# ard.net
KiCad netlist of a schematic drawn in EAGLE
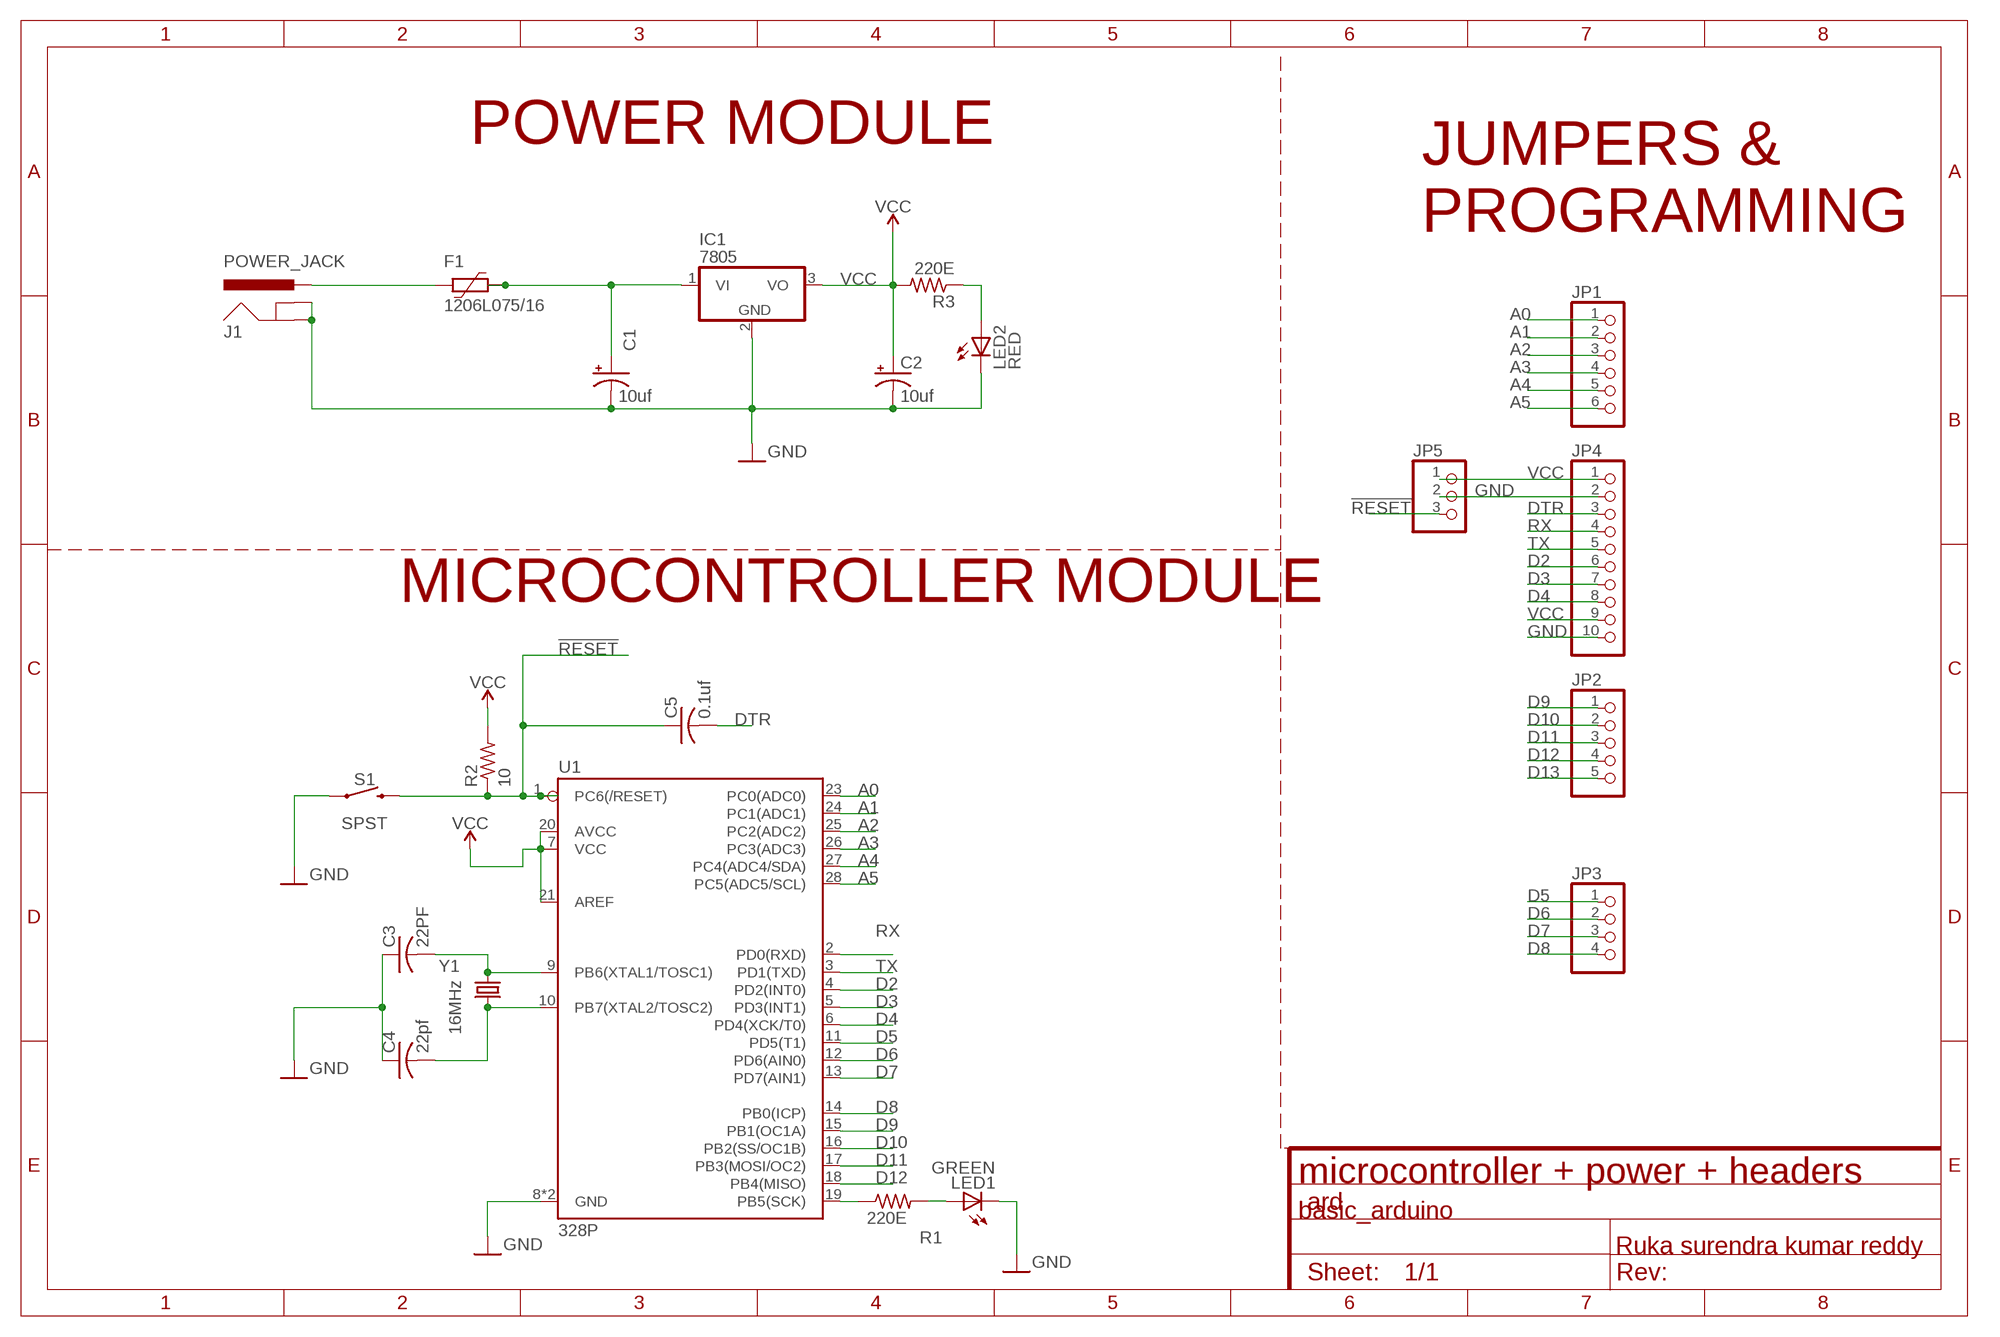
[diagram p0: schematic, sheet 1]

(export (version "E")
  (design (tool "Eeschema 10.0.6"))
  (components
    (comp (ref "C1")
      (value "10uf")
      (footprint "eagle-import:E2,5-6E")
      (libsource (lib "eagle-import") (part "CPOL-USE2,5-6E"))
    )
    (comp (ref "C2")
      (value "10uf")
      (footprint "eagle-import:E2,5-6E")
      (libsource (lib "eagle-import") (part "CPOL-USE2,5-6E"))
    )
    (comp (ref "C3")
      (value "22PF")
      (footprint "eagle-import:C025-024X044")
      (libsource (lib "eagle-import") (part "C-US025-024X044"))
    )
    (comp (ref "C4")
      (value "22pf")
      (footprint "eagle-import:C025-024X044")
      (libsource (lib "eagle-import") (part "C-US025-024X044"))
    )
    (comp (ref "C5")
      (value "0.1uf")
      (footprint "eagle-import:C025-024X044")
      (libsource (lib "eagle-import") (part "C-US025-024X044"))
    )
    (comp (ref "F1")
      (value "1206L075/16")
      (footprint "eagle-import:1206L")
      (fields (field (name "MF") "Littelfuse"))
      (libsource (lib "eagle-import") (part "?1206L075/16"))
    )
    (comp (ref "IC1")
      (value "7805")
      (footprint "eagle-import:TO220V")
      (libsource (lib "eagle-import") (part "78TV05"))
    )
    (comp (ref "J1")
      (value "POWER_JACK")
      (footprint "eagle-import:POWER_JACK_PTH")
      (libsource (lib "eagle-import") (part "POWER_JACK"))
    )
    (comp (ref "JP1")
      (value "PINHD-1X6")
      (footprint "eagle-import:1X06")
      (libsource (lib "eagle-import") (part "PINHD-1X6"))
    )
    (comp (ref "JP2")
      (value "PINHD-1X5")
      (footprint "eagle-import:1X05")
      (libsource (lib "eagle-import") (part "PINHD-1X5"))
    )
    (comp (ref "JP3")
      (value "PINHD-1X4")
      (footprint "eagle-import:1X04")
      (libsource (lib "eagle-import") (part "PINHD-1X4"))
    )
    (comp (ref "JP4")
      (value "PINHD-1X10")
      (footprint "eagle-import:1X10")
      (libsource (lib "eagle-import") (part "PINHD-1X10"))
    )
    (comp (ref "JP5")
      (value "PINHD-1X3")
      (footprint "eagle-import:1X03")
      (libsource (lib "eagle-import") (part "PINHD-1X3"))
    )
    (comp (ref "LED1")
      (value "GREEN")
      (footprint "eagle-import:LED5MM")
      (libsource (lib "eagle-import") (part "LED5MM"))
    )
    (comp (ref "LED2")
      (value "RED")
      (footprint "eagle-import:LED5MM")
      (libsource (lib "eagle-import") (part "LED5MM"))
    )
    (comp (ref "R1")
      (value "220E")
      (footprint "eagle-import:0204_7")
      (libsource (lib "eagle-import") (part "R-US_0204/7"))
    )
    (comp (ref "R2")
      (value "10")
      (footprint "eagle-import:0204_7")
      (libsource (lib "eagle-import") (part "R-US_0204/7"))
    )
    (comp (ref "R3")
      (value "220E")
      (footprint "eagle-import:0204_7")
      (libsource (lib "eagle-import") (part "R-US_0204/7"))
    )
    (comp (ref "S1")
      (value "SPST")
      (footprint "eagle-import:TACTILE_SWITCH_PTH_6.0MM")
      (libsource (lib "eagle-import") (part "MOMENTARY-SWITCH-SPST-PTH-6.0MM"))
    )
    (comp (ref "U1")
      (value "328P")
      (footprint "eagle-import:DIP28")
      (libsource (lib "eagle-import") (part "ATMEGA328P_PDIP"))
    )
    (comp (ref "Y1")
      (value "16MHz")
      (footprint "eagle-import:HC49US")
      (libsource (lib "eagle-import") (part "CRYSTAL-16MHZPTH-HC49US"))
    )
  )
  (nets
    (net (code "1") (name "/A0") (class "Default")
      (node (ref "JP1") (pin "1") (pinfunction "1_1") (pintype "passive"))
      (node (ref "U1") (pin "23") (pinfunction "PC0(ADC0)_23") (pintype "bidirectional"))
    )
    (net (code "2") (name "/A1") (class "Default")
      (node (ref "JP1") (pin "2") (pinfunction "2_2") (pintype "passive"))
      (node (ref "U1") (pin "24") (pinfunction "PC1(ADC1)_24") (pintype "bidirectional"))
    )
    (net (code "3") (name "/A2") (class "Default")
      (node (ref "JP1") (pin "3") (pinfunction "3_3") (pintype "passive"))
      (node (ref "U1") (pin "25") (pinfunction "PC2(ADC2)_25") (pintype "bidirectional"))
    )
    (net (code "4") (name "/A3") (class "Default")
      (node (ref "JP1") (pin "4") (pinfunction "4_4") (pintype "passive"))
      (node (ref "U1") (pin "26") (pinfunction "PC3(ADC3)_26") (pintype "bidirectional"))
    )
    (net (code "5") (name "/A4") (class "Default")
      (node (ref "JP1") (pin "5") (pinfunction "5_5") (pintype "passive"))
      (node (ref "U1") (pin "27") (pinfunction "PC4(ADC4/SDA)_27") (pintype "bidirectional"))
    )
    (net (code "6") (name "/A5") (class "Default")
      (node (ref "JP1") (pin "6") (pinfunction "6_6") (pintype "passive"))
      (node (ref "U1") (pin "28") (pinfunction "PC5(ADC5/SCL)_28") (pintype "bidirectional"))
    )
    (net (code "7") (name "/D2") (class "Default")
      (node (ref "JP4") (pin "6") (pinfunction "6_6") (pintype "passive"))
      (node (ref "U1") (pin "4") (pinfunction "PD2(INT0)_4") (pintype "bidirectional"))
    )
    (net (code "8") (name "/D3") (class "Default")
      (node (ref "JP4") (pin "7") (pinfunction "7_7") (pintype "passive"))
      (node (ref "U1") (pin "5") (pinfunction "PD3(INT1)_5") (pintype "bidirectional"))
    )
    (net (code "9") (name "/D4") (class "Default")
      (node (ref "JP4") (pin "8") (pinfunction "8_8") (pintype "passive"))
      (node (ref "U1") (pin "6") (pinfunction "PD4(XCK/T0)_6") (pintype "bidirectional"))
    )
    (net (code "10") (name "/D5") (class "Default")
      (node (ref "JP3") (pin "1") (pinfunction "1_1") (pintype "passive"))
      (node (ref "U1") (pin "11") (pinfunction "PD5(T1)_11") (pintype "bidirectional"))
    )
    (net (code "11") (name "/D6") (class "Default")
      (node (ref "JP3") (pin "2") (pinfunction "2_2") (pintype "passive"))
      (node (ref "U1") (pin "12") (pinfunction "PD6(AIN0)_12") (pintype "bidirectional"))
    )
    (net (code "12") (name "/D7") (class "Default")
      (node (ref "JP3") (pin "3") (pinfunction "3_3") (pintype "passive"))
      (node (ref "U1") (pin "13") (pinfunction "PD7(AIN1)_13") (pintype "bidirectional"))
    )
    (net (code "13") (name "/D8") (class "Default")
      (node (ref "JP3") (pin "4") (pinfunction "4_4") (pintype "passive"))
      (node (ref "U1") (pin "14") (pinfunction "PB0(ICP)_14") (pintype "bidirectional"))
    )
    (net (code "14") (name "/D9") (class "Default")
      (node (ref "JP2") (pin "1") (pinfunction "1_1") (pintype "passive"))
      (node (ref "U1") (pin "15") (pinfunction "PB1(OC1A)_15") (pintype "bidirectional"))
    )
    (net (code "15") (name "/D10") (class "Default")
      (node (ref "JP2") (pin "2") (pinfunction "2_2") (pintype "passive"))
      (node (ref "U1") (pin "16") (pinfunction "PB2(SS/OC1B)_16") (pintype "bidirectional"))
    )
    (net (code "16") (name "/D11") (class "Default")
      (node (ref "JP2") (pin "3") (pinfunction "3_3") (pintype "passive"))
      (node (ref "U1") (pin "17") (pinfunction "PB3(MOSI/OC2)_17") (pintype "bidirectional"))
    )
    (net (code "17") (name "/D12") (class "Default")
      (node (ref "JP2") (pin "4") (pinfunction "4_4") (pintype "passive"))
      (node (ref "U1") (pin "18") (pinfunction "PB4(MISO)_18") (pintype "bidirectional"))
    )
    (net (code "18") (name "/D13") (class "Default")
      (node (ref "JP2") (pin "5") (pinfunction "5_5") (pintype "passive"))
      (node (ref "R1") (pin "1") (pinfunction "1_1") (pintype "passive"))
      (node (ref "U1") (pin "19") (pinfunction "PB5(SCK)_19") (pintype "bidirectional"))
    )
    (net (code "19") (name "/DTR") (class "Default")
      (node (ref "C5") (pin "2") (pinfunction "2_2") (pintype "passive"))
      (node (ref "JP4") (pin "3") (pinfunction "3_3") (pintype "passive"))
    )
    (net (code "20") (name "/RX") (class "Default")
      (node (ref "JP4") (pin "4") (pinfunction "4_4") (pintype "passive"))
      (node (ref "U1") (pin "2") (pinfunction "PD0(RXD)_2") (pintype "bidirectional"))
    )
    (net (code "21") (name "/TX") (class "Default")
      (node (ref "JP4") (pin "5") (pinfunction "5_5") (pintype "passive"))
      (node (ref "U1") (pin "3") (pinfunction "PD1(TXD)_3") (pintype "bidirectional"))
    )
    (net (code "22") (name "/~{RESET}") (class "Default")
      (node (ref "C5") (pin "1") (pinfunction "1_1") (pintype "passive"))
      (node (ref "JP5") (pin "3") (pinfunction "3_3") (pintype "passive"))
      (node (ref "R2") (pin "1") (pinfunction "1_1") (pintype "passive"))
      (node (ref "S1") (pin "3") (pinfunction "2_3") (pintype "passive"))
      (node (ref "U1") (pin "1") (pinfunction "PC6(/RESET)_1") (pintype "bidirectional"))
    )
    (net (code "23") (name "GND") (class "Default")
      (node (ref "C1") (pin "-") (pinfunction "-_-") (pintype "passive"))
      (node (ref "C2") (pin "-") (pinfunction "-_-") (pintype "passive"))
      (node (ref "C3") (pin "1") (pinfunction "1_1") (pintype "passive"))
      (node (ref "C4") (pin "1") (pinfunction "1_1") (pintype "passive"))
      (node (ref "IC1") (pin "2") (pinfunction "GND_2") (pintype "passive"))
      (node (ref "J1") (pin "GND") (pinfunction "GND_GND") (pintype "bidirectional"))
      (node (ref "J1") (pin "GNDBREAK") (pinfunction "GNDBREAK_GNDBREAK") (pintype "bidirectional"))
      (node (ref "JP4") (pin "10") (pinfunction "10_10") (pintype "passive"))
      (node (ref "JP4") (pin "2") (pinfunction "2_2") (pintype "passive"))
      (node (ref "JP5") (pin "2") (pinfunction "2_2") (pintype "passive"))
      (node (ref "LED1") (pin "K") (pinfunction "C_K") (pintype "passive"))
      (node (ref "LED2") (pin "K") (pinfunction "C_K") (pintype "passive"))
      (node (ref "S1") (pin "1") (pinfunction "1_1") (pintype "passive"))
      (node (ref "U1") (pin "22") (pinfunction "GND_22") (pintype "bidirectional"))
      (node (ref "U1") (pin "8") (pinfunction "GND_8") (pintype "bidirectional"))
    )
    (net (code "24") (name "Net-(F1-Pad2)") (class "Default")
      (node (ref "F1") (pin "2") (pinfunction "2_2") (pintype "passive"))
      (node (ref "J1") (pin "PWR") (pinfunction "PWR_PWR") (pintype "bidirectional"))
    )
    (net (code "25") (name "Net-(IC1-VI)") (class "Default")
      (node (ref "C1") (pin "+") (pinfunction "+_+") (pintype "passive"))
      (node (ref "F1") (pin "1") (pinfunction "1_1") (pintype "passive"))
      (node (ref "IC1") (pin "1") (pinfunction "VI_1") (pintype "input"))
    )
    (net (code "26") (name "Net-(LED1-PadA)") (class "Default")
      (node (ref "LED1") (pin "A") (pinfunction "A_A") (pintype "passive"))
      (node (ref "R1") (pin "2") (pinfunction "2_2") (pintype "passive"))
    )
    (net (code "27") (name "Net-(LED2-PadA)") (class "Default")
      (node (ref "LED2") (pin "A") (pinfunction "A_A") (pintype "passive"))
      (node (ref "R3") (pin "1") (pinfunction "1_1") (pintype "passive"))
    )
    (net (code "28") (name "Net-(U1-PB6(XTAL1{slash}TOSC1))") (class "Default")
      (node (ref "C3") (pin "2") (pinfunction "2_2") (pintype "passive"))
      (node (ref "U1") (pin "9") (pinfunction "PB6(XTAL1/TOSC1)_9") (pintype "bidirectional"))
      (node (ref "Y1") (pin "1") (pinfunction "1_1") (pintype "passive"))
    )
    (net (code "29") (name "Net-(U1-PB7(XTAL2{slash}TOSC2))") (class "Default")
      (node (ref "C4") (pin "2") (pinfunction "2_2") (pintype "passive"))
      (node (ref "U1") (pin "10") (pinfunction "PB7(XTAL2/TOSC2)_10") (pintype "bidirectional"))
      (node (ref "Y1") (pin "2") (pinfunction "2_2") (pintype "passive"))
    )
    (net (code "30") (name "VCC") (class "Default")
      (node (ref "C2") (pin "+") (pinfunction "+_+") (pintype "passive"))
      (node (ref "IC1") (pin "3") (pinfunction "VO_3") (pintype "passive"))
      (node (ref "JP4") (pin "1") (pinfunction "1_1") (pintype "passive"))
      (node (ref "JP4") (pin "9") (pinfunction "9_9") (pintype "passive"))
      (node (ref "JP5") (pin "1") (pinfunction "1_1") (pintype "passive"))
      (node (ref "R2") (pin "2") (pinfunction "2_2") (pintype "passive"))
      (node (ref "R3") (pin "2") (pinfunction "2_2") (pintype "passive"))
      (node (ref "U1") (pin "20") (pinfunction "AVCC_20") (pintype "bidirectional"))
      (node (ref "U1") (pin "21") (pinfunction "AREF_21") (pintype "bidirectional"))
      (node (ref "U1") (pin "7") (pinfunction "VCC_7") (pintype "bidirectional"))
    )
  )
)
